# sbc_245.net
KiCad netlist of a schematic drawn in EAGLE
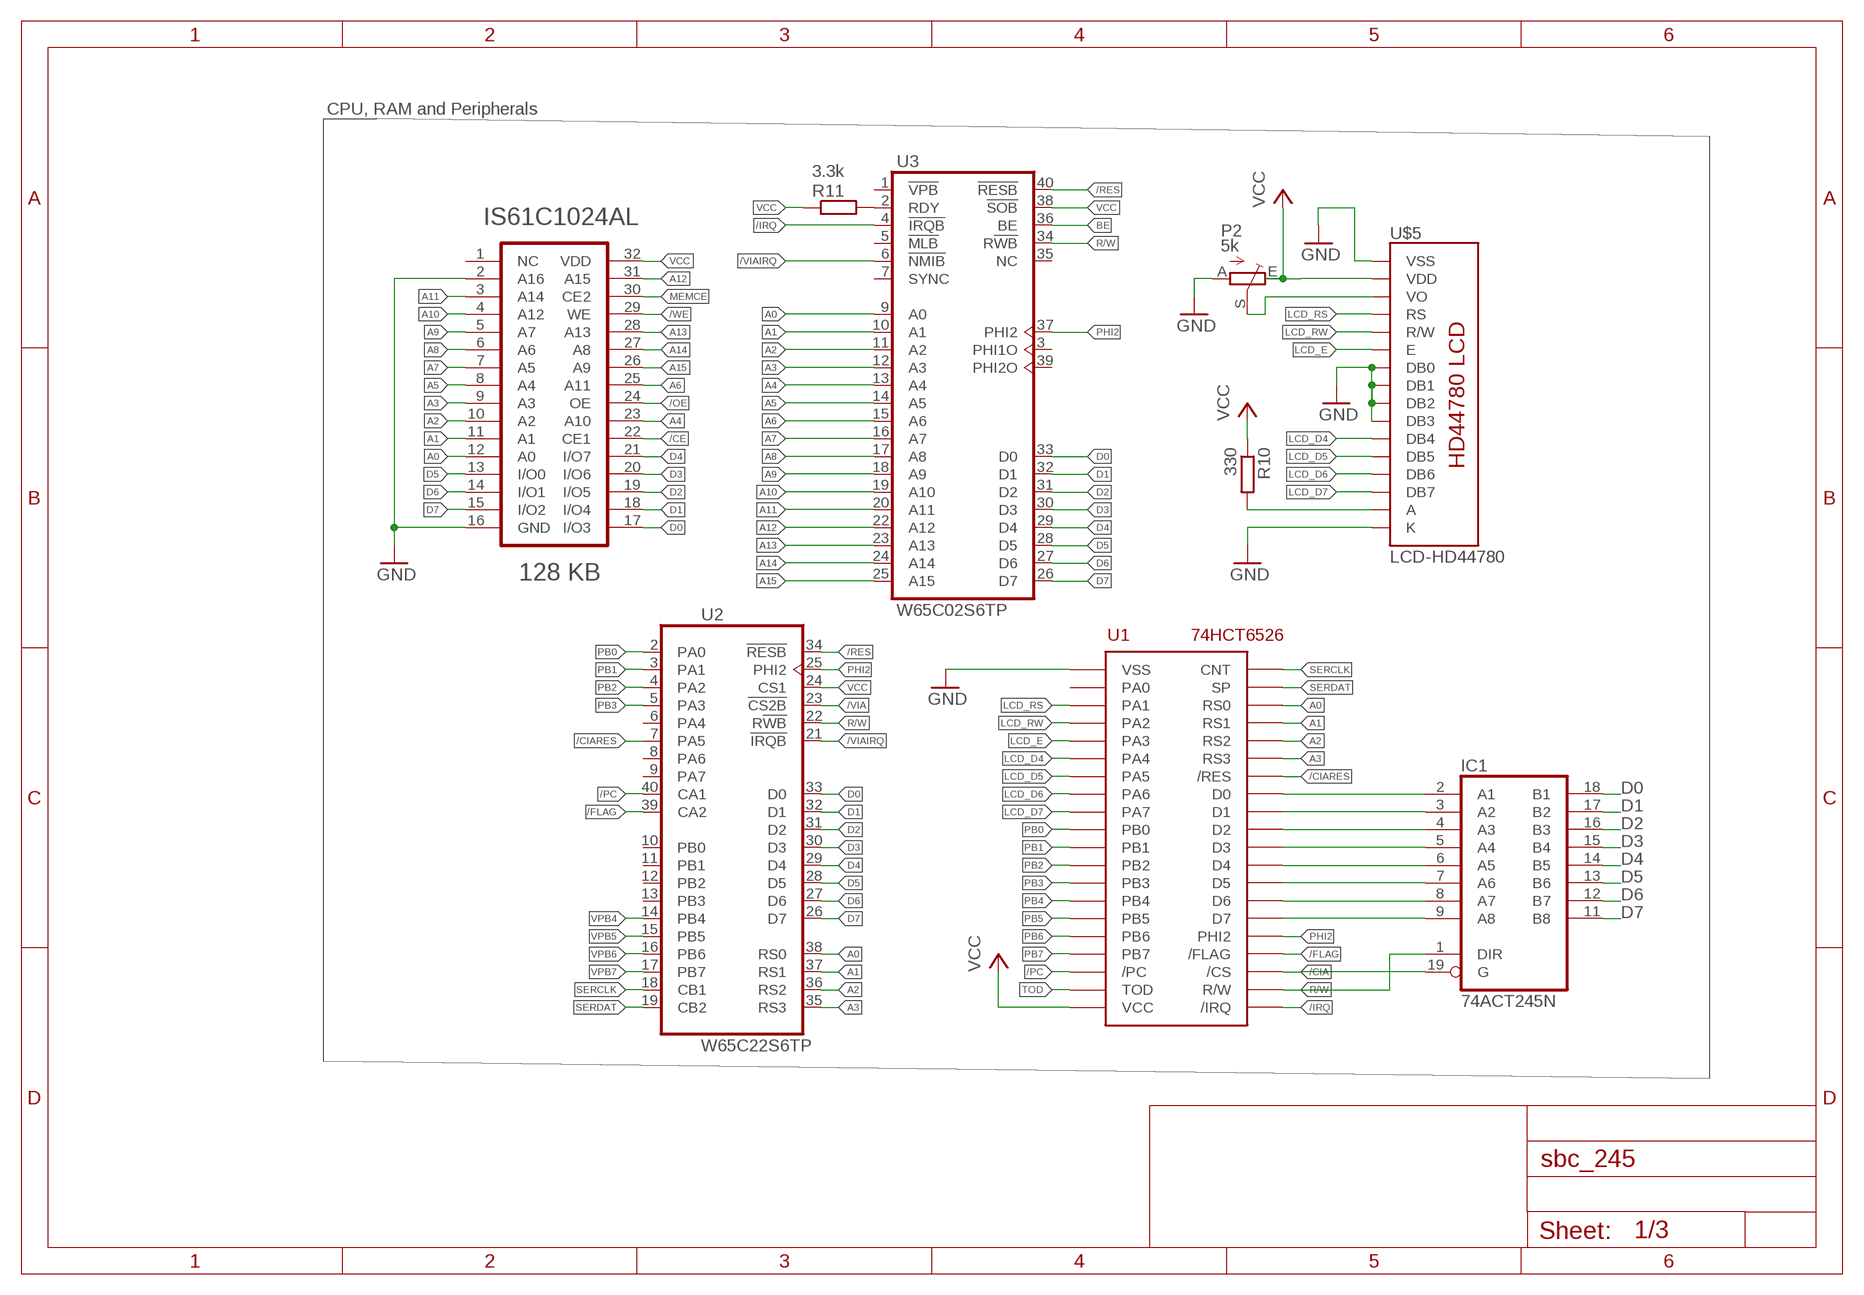
[diagram p0: schematic, sheet 1]
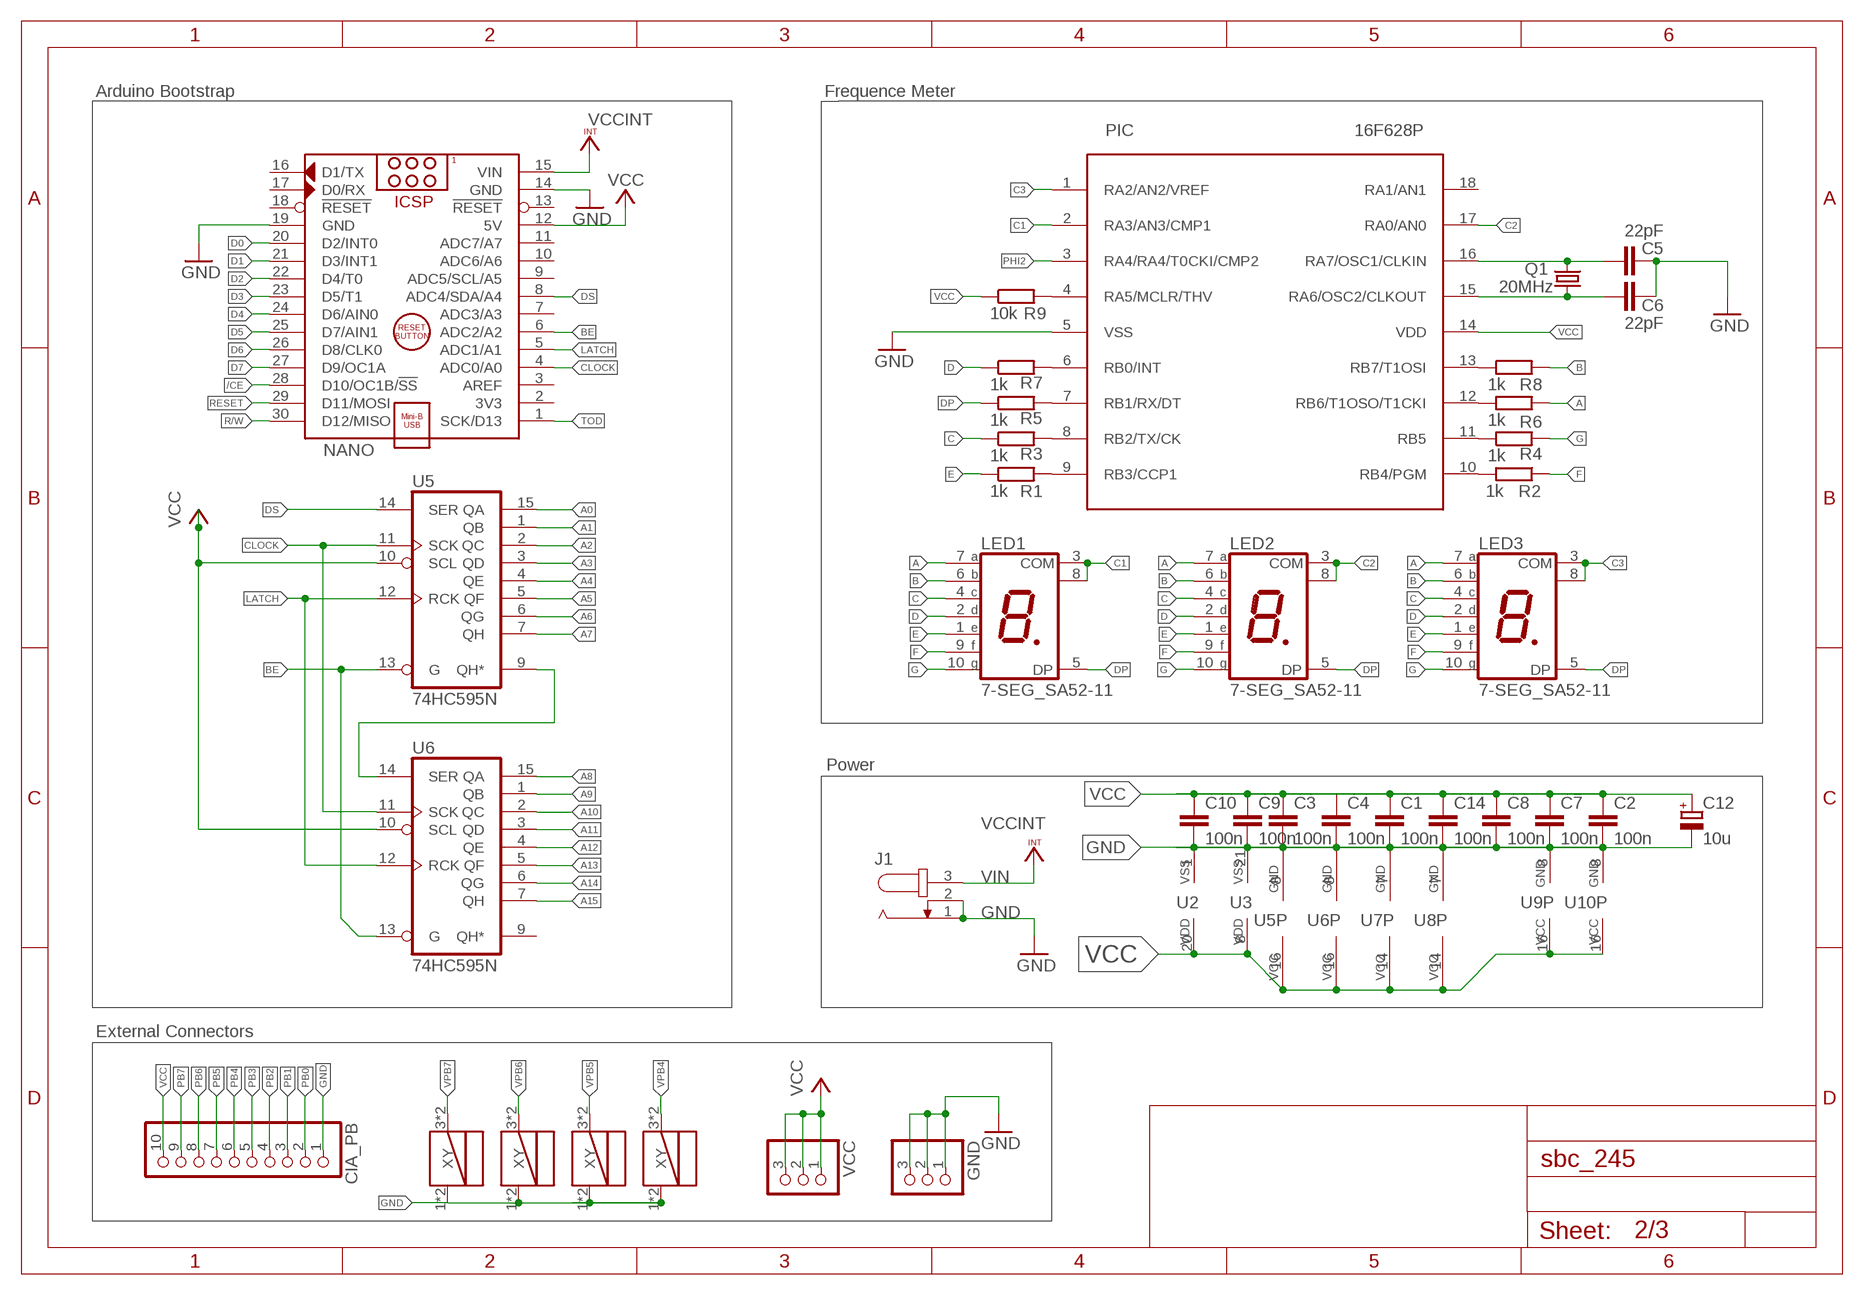
[diagram p1: schematic, sheet 2]
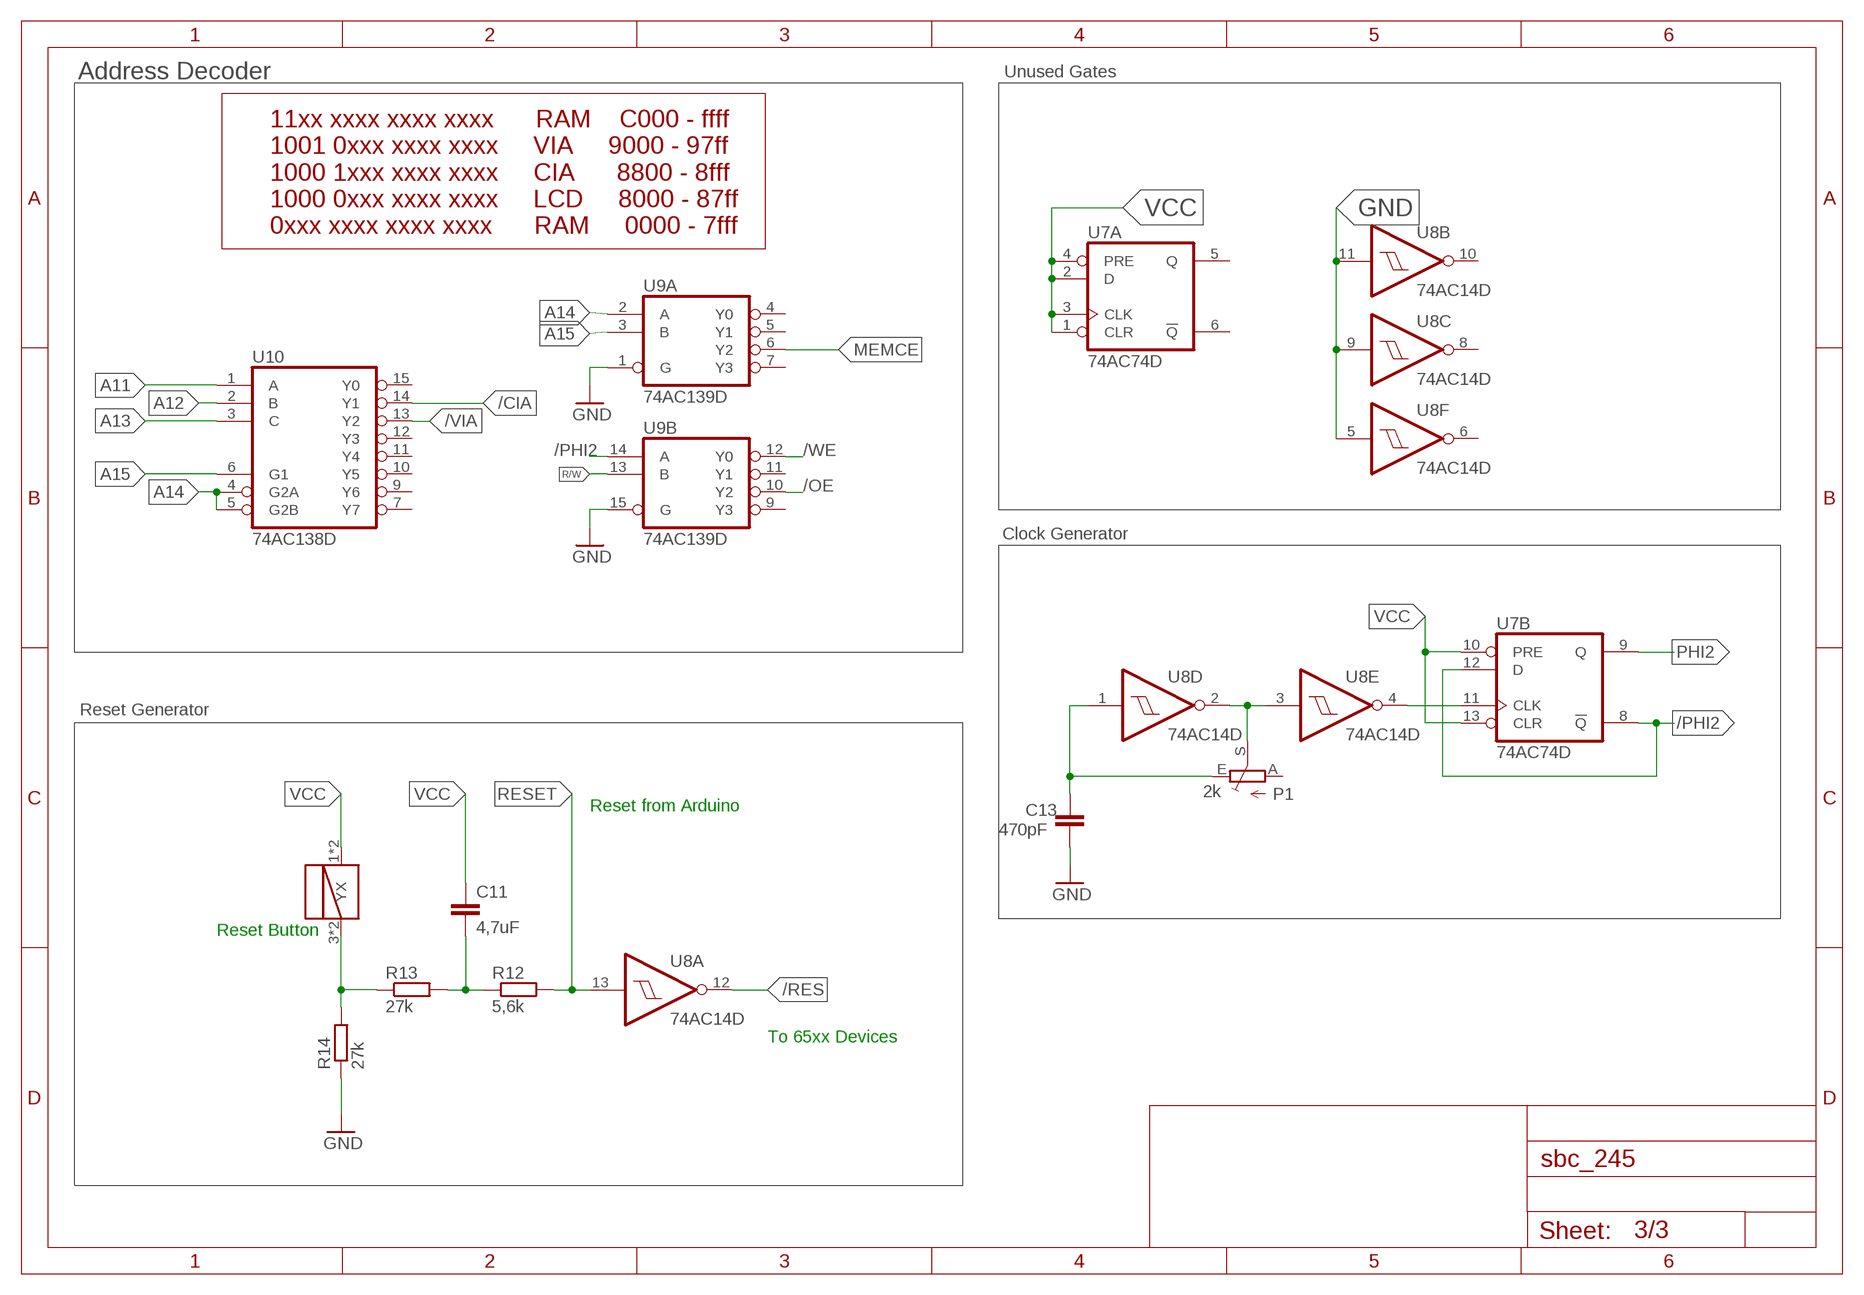
[diagram p2: schematic, sheet 3]

(export (version "E")
  (design (tool "Eeschema 10.0.6"))
  (components
    (comp (ref "C1")
      (value "100n")
      (footprint "eagle-import:C0805")
      (libsource (lib "eagle-import") (part "C-EUC0805"))
    )
    (comp (ref "C2")
      (value "100n")
      (footprint "eagle-import:C0805")
      (libsource (lib "eagle-import") (part "C-EUC0805"))
    )
    (comp (ref "C3")
      (value "100n")
      (footprint "eagle-import:C0805")
      (libsource (lib "eagle-import") (part "C-EUC0805"))
    )
    (comp (ref "C4")
      (value "100n")
      (footprint "eagle-import:C0805")
      (libsource (lib "eagle-import") (part "C-EUC0805"))
    )
    (comp (ref "C5")
      (value "22pF")
      (footprint "eagle-import:C025-025X050")
      (libsource (lib "eagle-import") (part "C-EU025-025X050"))
    )
    (comp (ref "C6")
      (value "22pF")
      (footprint "eagle-import:C025-025X050")
      (libsource (lib "eagle-import") (part "C-EU025-025X050"))
    )
    (comp (ref "C7")
      (value "100n")
      (footprint "eagle-import:C0805")
      (libsource (lib "eagle-import") (part "C-EUC0805"))
    )
    (comp (ref "C8")
      (value "100n")
      (footprint "eagle-import:C0805")
      (libsource (lib "eagle-import") (part "C-EUC0805"))
    )
    (comp (ref "C9")
      (value "100n")
      (footprint "eagle-import:C0805")
      (libsource (lib "eagle-import") (part "C-EUC0805"))
    )
    (comp (ref "C10")
      (value "100n")
      (footprint "eagle-import:C0805")
      (libsource (lib "eagle-import") (part "C-EUC0805"))
    )
    (comp (ref "C12")
      (value "10u")
      (footprint "eagle-import:B45181A")
      (libsource (lib "eagle-import") (part "CPOL-EUB45181A"))
    )
    (comp (ref "C14")
      (value "100n")
      (footprint "eagle-import:C0805")
      (libsource (lib "eagle-import") (part "C-EUC0805"))
    )
    (comp (ref "CIA_PB")
      (value "PINHD-1X10")
      (footprint "eagle-import:1X10")
      (libsource (lib "eagle-import") (part "PINHD-1X10"))
    )
    (comp (ref "GND")
      (value "PINHD-1X3")
      (footprint "eagle-import:1X03")
      (libsource (lib "eagle-import") (part "PINHD-1X3"))
    )
    (comp (ref "J1")
      (value "JACK-PLUG0")
      (footprint "eagle-import:SPC4077")
      (libsource (lib "eagle-import") (part "JACK-PLUG0"))
    )
    (comp (ref "LED1")
      (value "7-SEG_SA52-11")
      (footprint "eagle-import:SA52-11")
      (libsource (lib "eagle-import") (part "7-SEG_SA52-11"))
    )
    (comp (ref "LED2")
      (value "7-SEG_SA52-11")
      (footprint "eagle-import:SA52-11")
      (libsource (lib "eagle-import") (part "7-SEG_SA52-11"))
    )
    (comp (ref "LED3")
      (value "7-SEG_SA52-11")
      (footprint "eagle-import:SA52-11")
      (libsource (lib "eagle-import") (part "7-SEG_SA52-11"))
    )
    (comp (ref "NANO")
      (value "ARDUINO_NANO")
      (footprint "eagle-import:ARDUINO_NANO")
      (libsource (lib "eagle-import") (part "ARDUINO_NANO"))
    )
    (comp (ref "PIC")
      (value "16F628P")
      (footprint "eagle-import:DIL18")
      (libsource (lib "eagle-import") (part "16F62P8"))
    )
    (comp (ref "Q1")
      (value "20MHz")
      (footprint "eagle-import:HC18U-V")
      (libsource (lib "eagle-import") (part "CRYSTALHC18U-V"))
    )
    (comp (ref "R1")
      (value "1k")
      (footprint "eagle-import:0207_7")
      (libsource (lib "eagle-import") (part "R-EU_0207/7"))
    )
    (comp (ref "R2")
      (value "1k")
      (footprint "eagle-import:0207_7")
      (libsource (lib "eagle-import") (part "R-EU_0207/7"))
    )
    (comp (ref "R3")
      (value "1k")
      (footprint "eagle-import:0207_7")
      (libsource (lib "eagle-import") (part "R-EU_0207/7"))
    )
    (comp (ref "R4")
      (value "1k")
      (footprint "eagle-import:0207_7")
      (libsource (lib "eagle-import") (part "R-EU_0207/7"))
    )
    (comp (ref "R5")
      (value "1k")
      (footprint "eagle-import:0207_7")
      (libsource (lib "eagle-import") (part "R-EU_0207/7"))
    )
    (comp (ref "R6")
      (value "1k")
      (footprint "eagle-import:0207_7")
      (libsource (lib "eagle-import") (part "R-EU_0207/7"))
    )
    (comp (ref "R7")
      (value "1k")
      (footprint "eagle-import:0207_7")
      (libsource (lib "eagle-import") (part "R-EU_0207/7"))
    )
    (comp (ref "R8")
      (value "1k")
      (footprint "eagle-import:0207_7")
      (libsource (lib "eagle-import") (part "R-EU_0207/7"))
    )
    (comp (ref "R9")
      (value "10k")
      (footprint "eagle-import:R0805")
      (libsource (lib "eagle-import") (part "R-EU_R0805"))
    )
    (comp (ref "U$1")
      (value "TSA451G90-250")
      (footprint "eagle-import:TSA451G90-250")
      (libsource (lib "eagle-import") (part "TSA451G90-250"))
    )
    (comp (ref "U$2")
      (value "TSA451G90-250")
      (footprint "eagle-import:TSA451G90-250")
      (libsource (lib "eagle-import") (part "TSA451G90-250"))
    )
    (comp (ref "U$3")
      (value "TSA451G90-250")
      (footprint "eagle-import:TSA451G90-250")
      (libsource (lib "eagle-import") (part "TSA451G90-250"))
    )
    (comp (ref "U$4")
      (value "TSA451G90-250")
      (footprint "eagle-import:TSA451G90-250")
      (libsource (lib "eagle-import") (part "TSA451G90-250"))
    )
    (comp (ref "U2")
      (value "W65C22S6TP")
      (footprint "eagle-import:DIL40")
      (libsource (lib "eagle-import") (part "W65C22SP6T"))
    )
    (comp (ref "U3")
      (value "W65C02S6TP")
      (footprint "eagle-import:DIL40")
      (libsource (lib "eagle-import") (part "W65C02SP6T"))
    )
    (comp (ref "U5")
      (value "74HC595N")
      (footprint "eagle-import:SO16")
      (libsource (lib "eagle-import") (part "74595DLS"))
    )
    (comp (ref "U6")
      (value "74HC595N")
      (footprint "eagle-import:SO16")
      (libsource (lib "eagle-import") (part "74595DLS"))
    )
    (comp (ref "U7")
      (value "74AC74D")
      (footprint "eagle-import:SO14")
      (libsource (lib "eagle-import") (part "7474DLS"))
    )
    (comp (ref "U8")
      (value "74AC14D")
      (footprint "eagle-import:SO14")
      (libsource (lib "eagle-import") (part "7414D"))
    )
    (comp (ref "U9")
      (value "74AC139D")
      (footprint "eagle-import:SO16")
      (libsource (lib "eagle-import") (part "74139DAC"))
    )
    (comp (ref "U10")
      (value "74AC138D")
      (footprint "eagle-import:SO16")
      (libsource (lib "eagle-import") (part "74138DAC"))
    )
    (comp (ref "VCC")
      (value "PINHD-1X3")
      (footprint "eagle-import:1X03")
      (libsource (lib "eagle-import") (part "PINHD-1X3"))
    )
    (comp (ref "IC1")
      (value "74ACT245N")
      (footprint "eagle-import:DIL20")
      (libsource (lib "eagle-import") (part "74245NACT"))
    )
    (comp (ref "P2")
      (value "5k")
      (footprint "eagle-import:B64Y")
      (libsource (lib "eagle-import") (part "TRIM_EU-B64Y"))
    )
    (comp (ref "R10")
      (value "330")
      (footprint "eagle-import:R0805")
      (libsource (lib "eagle-import") (part "R-EU_R0805"))
    )
    (comp (ref "R11")
      (value "3.3k")
      (footprint "eagle-import:R0805")
      (libsource (lib "eagle-import") (part "R-EU_R0805"))
    )
    (comp (ref "U$5")
      (value "LCD-HD44780")
      (footprint "eagle-import:LCD-20X4-4HOLES2X8")
      (libsource (lib "eagle-import") (part "LCD-HD44780"))
    )
    (comp (ref "U1")
      (value "74HCT6526")
      (footprint "eagle-import:DIP40")
      (libsource (lib "eagle-import") (part "CIA40CIA_DIP"))
    )
    (comp (ref "U4")
      (value "IS61C1024AL-12JLI-TR")
      (footprint "eagle-import:SOJ32_3")
      (libsource (lib "eagle-import") (part "IS61C1024AL"))
    )
    (comp (ref "C11")
      (value "4,7uF")
      (footprint "eagle-import:C0805")
      (libsource (lib "eagle-import") (part "C-EUC0805"))
    )
    (comp (ref "C13")
      (value "470pF")
      (footprint "eagle-import:C0805")
      (libsource (lib "eagle-import") (part "C-EUC0805"))
    )
    (comp (ref "P1")
      (value "2k")
      (footprint "eagle-import:B64Y")
      (libsource (lib "eagle-import") (part "TRIM_EU-B64Y"))
    )
    (comp (ref "R12")
      (value "5,6k")
      (footprint "eagle-import:R0805")
      (libsource (lib "eagle-import") (part "R-EU_R0805"))
    )
    (comp (ref "R13")
      (value "27k")
      (footprint "eagle-import:R0805")
      (libsource (lib "eagle-import") (part "R-EU_R0805"))
    )
    (comp (ref "R14")
      (value "27k")
      (footprint "eagle-import:R0805")
      (libsource (lib "eagle-import") (part "R-EU_R0805"))
    )
    (comp (ref "SW1")
      (value "TSA451G90-250")
      (footprint "eagle-import:TSA451G90-250")
      (libsource (lib "eagle-import") (part "TSA451G90-250"))
    )
  )
  (nets
    (net (code "1") (name "A") (class "Default")
      (node (ref "LED1") (pin "7") (pinfunction "A_7") (pintype "passive"))
      (node (ref "LED2") (pin "7") (pinfunction "A_7") (pintype "passive"))
      (node (ref "LED3") (pin "7") (pinfunction "A_7") (pintype "passive"))
      (node (ref "R6") (pin "2") (pinfunction "2_2") (pintype "passive"))
    )
    (net (code "2") (name "A0") (class "Default")
      (node (ref "U1") (pin "38") (pinfunction "RS0_38") (pintype "bidirectional"))
      (node (ref "U2") (pin "38") (pinfunction "RS0_38") (pintype "input"))
      (node (ref "U3") (pin "9") (pinfunction "A0_9") (pintype "output"))
      (node (ref "U4") (pin "12") (pinfunction "A0_12") (pintype "bidirectional"))
      (node (ref "U5") (pin "15") (pinfunction "QA_15") (pintype "tri_state"))
    )
    (net (code "3") (name "A1") (class "Default")
      (node (ref "U1") (pin "37") (pinfunction "RS1_37") (pintype "bidirectional"))
      (node (ref "U2") (pin "37") (pinfunction "RS1_37") (pintype "input"))
      (node (ref "U3") (pin "10") (pinfunction "A1_10") (pintype "output"))
      (node (ref "U4") (pin "11") (pinfunction "A1_11") (pintype "bidirectional"))
      (node (ref "U5") (pin "1") (pinfunction "QB_1") (pintype "tri_state"))
    )
    (net (code "4") (name "A2") (class "Default")
      (node (ref "U1") (pin "36") (pinfunction "RS2_36") (pintype "bidirectional"))
      (node (ref "U2") (pin "36") (pinfunction "RS2_36") (pintype "input"))
      (node (ref "U3") (pin "11") (pinfunction "A2_11") (pintype "output"))
      (node (ref "U4") (pin "10") (pinfunction "A2_10") (pintype "bidirectional"))
      (node (ref "U5") (pin "2") (pinfunction "QC_2") (pintype "tri_state"))
    )
    (net (code "5") (name "A3") (class "Default")
      (node (ref "U1") (pin "35") (pinfunction "RS3_35") (pintype "bidirectional"))
      (node (ref "U2") (pin "35") (pinfunction "RS3_35") (pintype "input"))
      (node (ref "U3") (pin "12") (pinfunction "A3_12") (pintype "output"))
      (node (ref "U4") (pin "9") (pinfunction "A3_9") (pintype "bidirectional"))
      (node (ref "U5") (pin "3") (pinfunction "QD_3") (pintype "tri_state"))
    )
    (net (code "6") (name "A4") (class "Default")
      (node (ref "U3") (pin "13") (pinfunction "A4_13") (pintype "output"))
      (node (ref "U4") (pin "23") (pinfunction "A10_23") (pintype "bidirectional"))
      (node (ref "U5") (pin "4") (pinfunction "QE_4") (pintype "tri_state"))
    )
    (net (code "7") (name "A5") (class "Default")
      (node (ref "U3") (pin "14") (pinfunction "A5_14") (pintype "output"))
      (node (ref "U4") (pin "8") (pinfunction "A4_8") (pintype "bidirectional"))
      (node (ref "U5") (pin "5") (pinfunction "QF_5") (pintype "tri_state"))
    )
    (net (code "8") (name "A6") (class "Default")
      (node (ref "U3") (pin "15") (pinfunction "A6_15") (pintype "output"))
      (node (ref "U4") (pin "25") (pinfunction "A11_25") (pintype "bidirectional"))
      (node (ref "U5") (pin "6") (pinfunction "QG_6") (pintype "tri_state"))
    )
    (net (code "9") (name "A7") (class "Default")
      (node (ref "U3") (pin "16") (pinfunction "A7_16") (pintype "output"))
      (node (ref "U4") (pin "7") (pinfunction "A5_7") (pintype "bidirectional"))
      (node (ref "U5") (pin "7") (pinfunction "QH_7") (pintype "tri_state"))
    )
    (net (code "10") (name "A8") (class "Default")
      (node (ref "U3") (pin "17") (pinfunction "A8_17") (pintype "output"))
      (node (ref "U4") (pin "6") (pinfunction "A6_6") (pintype "bidirectional"))
      (node (ref "U6") (pin "15") (pinfunction "QA_15") (pintype "tri_state"))
    )
    (net (code "11") (name "A9") (class "Default")
      (node (ref "U3") (pin "18") (pinfunction "A9_18") (pintype "output"))
      (node (ref "U4") (pin "5") (pinfunction "A7_5") (pintype "bidirectional"))
      (node (ref "U6") (pin "1") (pinfunction "QB_1") (pintype "tri_state"))
    )
    (net (code "12") (name "A10") (class "Default")
      (node (ref "U3") (pin "19") (pinfunction "A10_19") (pintype "output"))
      (node (ref "U4") (pin "4") (pinfunction "A12_4") (pintype "bidirectional"))
      (node (ref "U6") (pin "2") (pinfunction "QC_2") (pintype "tri_state"))
    )
    (net (code "13") (name "A11") (class "Default")
      (node (ref "U10") (pin "1") (pinfunction "A_1") (pintype "input"))
      (node (ref "U3") (pin "20") (pinfunction "A11_20") (pintype "output"))
      (node (ref "U4") (pin "3") (pinfunction "A14_3") (pintype "bidirectional"))
      (node (ref "U6") (pin "3") (pinfunction "QD_3") (pintype "tri_state"))
    )
    (net (code "14") (name "A12") (class "Default")
      (node (ref "U10") (pin "2") (pinfunction "B_2") (pintype "input"))
      (node (ref "U3") (pin "22") (pinfunction "A12_22") (pintype "output"))
      (node (ref "U4") (pin "31") (pinfunction "A15_31") (pintype "bidirectional"))
      (node (ref "U6") (pin "4") (pinfunction "QE_4") (pintype "tri_state"))
    )
    (net (code "15") (name "A13") (class "Default")
      (node (ref "U10") (pin "3") (pinfunction "C_3") (pintype "input"))
      (node (ref "U3") (pin "23") (pinfunction "A13_23") (pintype "output"))
      (node (ref "U4") (pin "28") (pinfunction "A13_28") (pintype "bidirectional"))
      (node (ref "U6") (pin "5") (pinfunction "QF_5") (pintype "tri_state"))
    )
    (net (code "16") (name "A14") (class "Default")
      (node (ref "U10") (pin "4") (pinfunction "G2A_4") (pintype "input"))
      (node (ref "U10") (pin "5") (pinfunction "G2B_5") (pintype "input"))
      (node (ref "U3") (pin "24") (pinfunction "A14_24") (pintype "output"))
      (node (ref "U4") (pin "27") (pinfunction "A8_27") (pintype "bidirectional"))
      (node (ref "U6") (pin "6") (pinfunction "QG_6") (pintype "tri_state"))
      (node (ref "U9") (pin "2") (pinfunction "A_2") (pintype "input"))
    )
    (net (code "17") (name "A15") (class "Default")
      (node (ref "U10") (pin "6") (pinfunction "G1_6") (pintype "input"))
      (node (ref "U3") (pin "25") (pinfunction "A15_25") (pintype "output"))
      (node (ref "U4") (pin "26") (pinfunction "A9_26") (pintype "bidirectional"))
      (node (ref "U6") (pin "7") (pinfunction "QH_7") (pintype "tri_state"))
      (node (ref "U9") (pin "3") (pinfunction "B_3") (pintype "input"))
    )
    (net (code "18") (name "B") (class "Default")
      (node (ref "LED1") (pin "6") (pinfunction "B_6") (pintype "passive"))
      (node (ref "LED2") (pin "6") (pinfunction "B_6") (pintype "passive"))
      (node (ref "LED3") (pin "6") (pinfunction "B_6") (pintype "passive"))
      (node (ref "R8") (pin "2") (pinfunction "2_2") (pintype "passive"))
    )
    (net (code "19") (name "BE") (class "Default")
      (node (ref "NANO") (pin "6") (pinfunction "ADC2/A2_6") (pintype "bidirectional"))
      (node (ref "U3") (pin "36") (pinfunction "BE_36") (pintype "input"))
      (node (ref "U5") (pin "13") (pinfunction "G_13") (pintype "input"))
      (node (ref "U6") (pin "13") (pinfunction "G_13") (pintype "input"))
    )
    (net (code "20") (name "C") (class "Default")
      (node (ref "LED1") (pin "4") (pinfunction "C_4") (pintype "passive"))
      (node (ref "LED2") (pin "4") (pinfunction "C_4") (pintype "passive"))
      (node (ref "LED3") (pin "4") (pinfunction "C_4") (pintype "passive"))
      (node (ref "R3") (pin "1") (pinfunction "1_1") (pintype "passive"))
    )
    (net (code "21") (name "C1") (class "Default")
      (node (ref "LED1") (pin "3") (pinfunction "COM_3") (pintype "passive"))
      (node (ref "LED1") (pin "8") (pinfunction "COM_8") (pintype "passive"))
      (node (ref "PIC") (pin "2") (pinfunction "RA3/AN3/CMP1_2") (pintype "bidirectional"))
    )
    (net (code "22") (name "C2") (class "Default")
      (node (ref "LED2") (pin "3") (pinfunction "COM_3") (pintype "passive"))
      (node (ref "LED2") (pin "8") (pinfunction "COM_8") (pintype "passive"))
      (node (ref "PIC") (pin "17") (pinfunction "RA0/AN0_17") (pintype "bidirectional"))
    )
    (net (code "23") (name "C3") (class "Default")
      (node (ref "LED3") (pin "3") (pinfunction "COM_3") (pintype "passive"))
      (node (ref "LED3") (pin "8") (pinfunction "COM_8") (pintype "passive"))
      (node (ref "PIC") (pin "1") (pinfunction "RA2/AN2/VREF_1") (pintype "bidirectional"))
    )
    (net (code "24") (name "CLOCK") (class "Default")
      (node (ref "NANO") (pin "4") (pinfunction "ADC0/A0_4") (pintype "bidirectional"))
      (node (ref "U5") (pin "11") (pinfunction "SCK_11") (pintype "input"))
      (node (ref "U6") (pin "11") (pinfunction "SCK_11") (pintype "input"))
    )
    (net (code "25") (name "D") (class "Default")
      (node (ref "LED1") (pin "2") (pinfunction "D_2") (pintype "passive"))
      (node (ref "LED2") (pin "2") (pinfunction "D_2") (pintype "passive"))
      (node (ref "LED3") (pin "2") (pinfunction "D_2") (pintype "passive"))
      (node (ref "R7") (pin "1") (pinfunction "1_1") (pintype "passive"))
    )
    (net (code "26") (name "D0") (class "Default")
      (node (ref "IC1") (pin "18") (pinfunction "B1_18") (pintype "bidirectional"))
      (node (ref "NANO") (pin "20") (pinfunction "D2/INT0_20") (pintype "bidirectional"))
      (node (ref "U2") (pin "33") (pinfunction "D0_33") (pintype "bidirectional"))
      (node (ref "U3") (pin "33") (pinfunction "D0_33") (pintype "bidirectional"))
      (node (ref "U4") (pin "17") (pinfunction "I/O3_17") (pintype "bidirectional"))
    )
    (net (code "27") (name "D1") (class "Default")
      (node (ref "IC1") (pin "17") (pinfunction "B2_17") (pintype "bidirectional"))
      (node (ref "NANO") (pin "21") (pinfunction "D3/INT1_21") (pintype "bidirectional"))
      (node (ref "U2") (pin "32") (pinfunction "D1_32") (pintype "bidirectional"))
      (node (ref "U3") (pin "32") (pinfunction "D1_32") (pintype "bidirectional"))
      (node (ref "U4") (pin "18") (pinfunction "I/O4_18") (pintype "bidirectional"))
    )
    (net (code "28") (name "D2") (class "Default")
      (node (ref "IC1") (pin "16") (pinfunction "B3_16") (pintype "bidirectional"))
      (node (ref "NANO") (pin "22") (pinfunction "D4/T0_22") (pintype "bidirectional"))
      (node (ref "U2") (pin "31") (pinfunction "D2_31") (pintype "bidirectional"))
      (node (ref "U3") (pin "31") (pinfunction "D2_31") (pintype "bidirectional"))
      (node (ref "U4") (pin "19") (pinfunction "I/O5_19") (pintype "bidirectional"))
    )
    (net (code "29") (name "D3") (class "Default")
      (node (ref "IC1") (pin "15") (pinfunction "B4_15") (pintype "bidirectional"))
      (node (ref "NANO") (pin "23") (pinfunction "D5/T1_23") (pintype "bidirectional"))
      (node (ref "U2") (pin "30") (pinfunction "D3_30") (pintype "bidirectional"))
      (node (ref "U3") (pin "30") (pinfunction "D3_30") (pintype "bidirectional"))
      (node (ref "U4") (pin "20") (pinfunction "I/O6_20") (pintype "bidirectional"))
    )
    (net (code "30") (name "D4") (class "Default")
      (node (ref "IC1") (pin "14") (pinfunction "B5_14") (pintype "bidirectional"))
      (node (ref "NANO") (pin "24") (pinfunction "D6/AIN0_24") (pintype "bidirectional"))
      (node (ref "U2") (pin "29") (pinfunction "D4_29") (pintype "bidirectional"))
      (node (ref "U3") (pin "29") (pinfunction "D4_29") (pintype "bidirectional"))
      (node (ref "U4") (pin "21") (pinfunction "I/O7_21") (pintype "bidirectional"))
    )
    (net (code "31") (name "D5") (class "Default")
      (node (ref "IC1") (pin "13") (pinfunction "B6_13") (pintype "bidirectional"))
      (node (ref "NANO") (pin "25") (pinfunction "D7/AIN1_25") (pintype "bidirectional"))
      (node (ref "U2") (pin "28") (pinfunction "D5_28") (pintype "bidirectional"))
      (node (ref "U3") (pin "28") (pinfunction "D5_28") (pintype "bidirectional"))
      (node (ref "U4") (pin "13") (pinfunction "I/O0_13") (pintype "bidirectional"))
    )
    (net (code "32") (name "D6") (class "Default")
      (node (ref "IC1") (pin "12") (pinfunction "B7_12") (pintype "bidirectional"))
      (node (ref "NANO") (pin "26") (pinfunction "D8/CLK0_26") (pintype "bidirectional"))
      (node (ref "U2") (pin "27") (pinfunction "D6_27") (pintype "bidirectional"))
      (node (ref "U3") (pin "27") (pinfunction "D6_27") (pintype "bidirectional"))
      (node (ref "U4") (pin "14") (pinfunction "I/O1_14") (pintype "bidirectional"))
    )
    (net (code "33") (name "D7") (class "Default")
      (node (ref "IC1") (pin "11") (pinfunction "B8_11") (pintype "bidirectional"))
      (node (ref "NANO") (pin "27") (pinfunction "D9/OC1A_27") (pintype "bidirectional"))
      (node (ref "U2") (pin "26") (pinfunction "D7_26") (pintype "bidirectional"))
      (node (ref "U3") (pin "26") (pinfunction "D7_26") (pintype "bidirectional"))
      (node (ref "U4") (pin "15") (pinfunction "I/O2_15") (pintype "bidirectional"))
    )
    (net (code "34") (name "DP") (class "Default")
      (node (ref "LED1") (pin "5") (pinfunction "DP_5") (pintype "passive"))
      (node (ref "LED2") (pin "5") (pinfunction "DP_5") (pintype "passive"))
      (node (ref "LED3") (pin "5") (pinfunction "DP_5") (pintype "passive"))
      (node (ref "R5") (pin "1") (pinfunction "1_1") (pintype "passive"))
    )
    (net (code "35") (name "DS") (class "Default")
      (node (ref "NANO") (pin "8") (pinfunction "ADC4/SDA/A4_8") (pintype "bidirectional"))
      (node (ref "U5") (pin "14") (pinfunction "SER_14") (pintype "input"))
    )
    (net (code "36") (name "E") (class "Default")
      (node (ref "LED1") (pin "1") (pinfunction "E_1") (pintype "passive"))
      (node (ref "LED2") (pin "1") (pinfunction "E_1") (pintype "passive"))
      (node (ref "LED3") (pin "1") (pinfunction "E_1") (pintype "passive"))
      (node (ref "R1") (pin "1") (pinfunction "1_1") (pintype "passive"))
    )
    (net (code "37") (name "F") (class "Default")
      (node (ref "LED1") (pin "9") (pinfunction "F_9") (pintype "passive"))
      (node (ref "LED2") (pin "9") (pinfunction "F_9") (pintype "passive"))
      (node (ref "LED3") (pin "9") (pinfunction "F_9") (pintype "passive"))
      (node (ref "R2") (pin "1") (pinfunction "1_1") (pintype "passive"))
    )
    (net (code "38") (name "G") (class "Default")
      (node (ref "LED1") (pin "10") (pinfunction "G_10") (pintype "passive"))
      (node (ref "LED2") (pin "10") (pinfunction "G_10") (pintype "passive"))
      (node (ref "LED3") (pin "10") (pinfunction "G_10") (pintype "passive"))
      (node (ref "R4") (pin "2") (pinfunction "2_2") (pintype "passive"))
    )
    (net (code "39") (name "GND") (class "Default")
      (node (ref "C1") (pin "2") (pinfunction "2_2") (pintype "passive"))
      (node (ref "C10") (pin "2") (pinfunction "2_2") (pintype "passive"))
      (node (ref "C12") (pin "-") (pinfunction "-_-") (pintype "passive"))
      (node (ref "C13") (pin "2") (pinfunction "2_2") (pintype "passive"))
      (node (ref "C14") (pin "2") (pinfunction "2_2") (pintype "passive"))
      (node (ref "C2") (pin "2") (pinfunction "2_2") (pintype "passive"))
      (node (ref "C3") (pin "2") (pinfunction "2_2") (pintype "passive"))
      (node (ref "C4") (pin "2") (pinfunction "2_2") (pintype "passive"))
      (node (ref "C5") (pin "2") (pinfunction "2_2") (pintype "passive"))
      (node (ref "C6") (pin "2") (pinfunction "2_2") (pintype "passive"))
      (node (ref "C7") (pin "2") (pinfunction "2_2") (pintype "passive"))
      (node (ref "C8") (pin "2") (pinfunction "2_2") (pintype "passive"))
      (node (ref "C9") (pin "2") (pinfunction "2_2") (pintype "passive"))
      (node (ref "CIA_PB") (pin "1") (pinfunction "1_1") (pintype "passive"))
      (node (ref "GND") (pin "1") (pinfunction "1_1") (pintype "passive"))
      (node (ref "GND") (pin "2") (pinfunction "2_2") (pintype "passive"))
      (node (ref "GND") (pin "3") (pinfunction "3_3") (pintype "passive"))
      (node (ref "J1") (pin "1") (pinfunction "1_1") (pintype "passive"))
      (node (ref "J1") (pin "2") (pinfunction "2_2") (pintype "passive"))
      (node (ref "NANO") (pin "14") (pinfunction "GND_14") (pintype "power_in"))
      (node (ref "NANO") (pin "19") (pinfunction "GND_19") (pintype "power_in"))
      (node (ref "P2") (pin "A") (pinfunction "A_A") (pintype "passive"))
      (node (ref "PIC") (pin "5") (pinfunction "VSS_5") (pintype "power_in"))
      (node (ref "R14") (pin "1") (pinfunction "1_1") (pintype "passive"))
      (node (ref "U$1") (pin "1") (pinfunction "X_1") (pintype "bidirectional"))
      (node (ref "U$1") (pin "2") (pinfunction "X_2") (pintype "bidirectional"))
      (node (ref "U$2") (pin "1") (pinfunction "X_1") (pintype "bidirectional"))
      (node (ref "U$2") (pin "2") (pinfunction "X_2") (pintype "bidirectional"))
      (node (ref "U$3") (pin "1") (pinfunction "X_1") (pintype "bidirectional"))
      (node (ref "U$3") (pin "2") (pinfunction "X_2") (pintype "bidirectional"))
      (node (ref "U$4") (pin "1") (pinfunction "X_1") (pintype "bidirectional"))
      (node (ref "U$4") (pin "2") (pinfunction "X_2") (pintype "bidirectional"))
      (node (ref "U$5") (pin "P$1") (pinfunction "VSS_P$1") (pintype "power_in"))
      (node (ref "U$5") (pin "P$10") (pinfunction "DB3_P$10") (pintype "bidirectional"))
      (node (ref "U$5") (pin "P$16") (pinfunction "K_P$16") (pintype "power_in"))
      (node (ref "U$5") (pin "P$7") (pinfunction "DB0_P$7") (pintype "bidirectional"))
      (node (ref "U$5") (pin "P$8") (pinfunction "DB1_P$8") (pintype "bidirectional"))
      (node (ref "U$5") (pin "P$9") (pinfunction "DB2_P$9") (pintype "bidirectional"))
      (node (ref "U1") (pin "1") (pinfunction "VSS_1") (pintype "bidirectional"))
      (node (ref "U10") (pin "8") (pinfunction "GND_8") (pintype "power_in"))
      (node (ref "U2") (pin "1") (pinfunction "VSS_1") (pintype "power_in"))
      (node (ref "U3") (pin "21") (pinfunction "VSS_21") (pintype "power_in"))
      (node (ref "U4") (pin "16") (pinfunction "GND_16") (pintype "bidirectional"))
      (node (ref "U4") (pin "2") (pinfunction "A16_2") (pintype "bidirectional"))
      (node (ref "U5") (pin "8") (pinfunction "GND_8") (pintype "power_in"))
      (node (ref "U6") (pin "8") (pinfunction "GND_8") (pintype "power_in"))
      (node (ref "U7") (pin "7") (pinfunction "GND_7") (pintype "power_in"))
      (node (ref "U8") (pin "11") (pinfunction "I_11") (pintype "input"))
      (node (ref "U8") (pin "5") (pinfunction "I_5") (pintype "input"))
      (node (ref "U8") (pin "7") (pinfunction "GND_7") (pintype "power_in"))
      (node (ref "U8") (pin "9") (pinfunction "I_9") (pintype "input"))
      (node (ref "U9") (pin "1") (pinfunction "G_1") (pintype "input"))
      (node (ref "U9") (pin "15") (pinfunction "G_15") (pintype "input"))
      (node (ref "U9") (pin "8") (pinfunction "GND_8") (pintype "power_in"))
    )
    (net (code "40") (name "LATCH") (class "Default")
      (node (ref "NANO") (pin "5") (pinfunction "ADC1/A1_5") (pintype "bidirectional"))
      (node (ref "U5") (pin "12") (pinfunction "RCK_12") (pintype "input"))
      (node (ref "U6") (pin "12") (pinfunction "RCK_12") (pintype "input"))
    )
    (net (code "41") (name "LCD_D4") (class "Default")
      (node (ref "U$5") (pin "P$11") (pinfunction "DB4_P$11") (pintype "bidirectional"))
      (node (ref "U1") (pin "6") (pinfunction "PA4_6") (pintype "bidirectional"))
    )
    (net (code "42") (name "LCD_D5") (class "Default")
      (node (ref "U$5") (pin "P$12") (pinfunction "DB5_P$12") (pintype "bidirectional"))
      (node (ref "U1") (pin "7") (pinfunction "PA5_7") (pintype "bidirectional"))
    )
    (net (code "43") (name "LCD_D6") (class "Default")
      (node (ref "U$5") (pin "P$13") (pinfunction "DB6_P$13") (pintype "bidirectional"))
      (node (ref "U1") (pin "8") (pinfunction "PA6_8") (pintype "bidirectional"))
    )
    (net (code "44") (name "LCD_D7") (class "Default")
      (node (ref "U$5") (pin "P$14") (pinfunction "DB7_P$14") (pintype "bidirectional"))
      (node (ref "U1") (pin "9") (pinfunction "PA7_9") (pintype "bidirectional"))
    )
    (net (code "45") (name "LCD_E") (class "Default")
      (node (ref "U$5") (pin "P$6") (pinfunction "E_P$6") (pintype "input"))
      (node (ref "U1") (pin "5") (pinfunction "PA3_5") (pintype "bidirectional"))
    )
    (net (code "46") (name "LCD_RS") (class "Default")
      (node (ref "U$5") (pin "P$4") (pinfunction "RS_P$4") (pintype "input"))
      (node (ref "U1") (pin "3") (pinfunction "PA1_3") (pintype "bidirectional"))
    )
    (net (code "47") (name "LCD_RW") (class "Default")
      (node (ref "U$5") (pin "P$5") (pinfunction "R/W_P$5") (pintype "input"))
      (node (ref "U1") (pin "4") (pinfunction "PA2_4") (pintype "bidirectional"))
    )
    (net (code "48") (name "MEMCE") (class "Default")
      (node (ref "U4") (pin "30") (pinfunction "CE2_30") (pintype "bidirectional"))
      (node (ref "U9") (pin "6") (pinfunction "Y2_6") (pintype "output"))
    )
    (net (code "49") (name "Net-(C11-Pad2)") (class "Default")
      (node (ref "C11") (pin "2") (pinfunction "2_2") (pintype "passive"))
      (node (ref "R12") (pin "1") (pinfunction "1_1") (pintype "passive"))
      (node (ref "R13") (pin "2") (pinfunction "2_2") (pintype "passive"))
    )
    (net (code "50") (name "Net-(IC1A-A1)") (class "Default")
      (node (ref "IC1") (pin "2") (pinfunction "A1_2") (pintype "bidirectional"))
      (node (ref "U1") (pin "33") (pinfunction "D0_33") (pintype "bidirectional"))
    )
    (net (code "51") (name "Net-(IC1A-A2)") (class "Default")
      (node (ref "IC1") (pin "3") (pinfunction "A2_3") (pintype "bidirectional"))
      (node (ref "U1") (pin "32") (pinfunction "D1_32") (pintype "bidirectional"))
    )
    (net (code "52") (name "Net-(IC1A-A3)") (class "Default")
      (node (ref "IC1") (pin "4") (pinfunction "A3_4") (pintype "bidirectional"))
      (node (ref "U1") (pin "31") (pinfunction "D2_31") (pintype "bidirectional"))
    )
    (net (code "53") (name "Net-(IC1A-A4)") (class "Default")
      (node (ref "IC1") (pin "5") (pinfunction "A4_5") (pintype "bidirectional"))
      (node (ref "U1") (pin "30") (pinfunction "D3_30") (pintype "bidirectional"))
    )
    (net (code "54") (name "Net-(IC1A-A5)") (class "Default")
      (node (ref "IC1") (pin "6") (pinfunction "A5_6") (pintype "bidirectional"))
      (node (ref "U1") (pin "29") (pinfunction "D4_29") (pintype "bidirectional"))
    )
    (net (code "55") (name "Net-(IC1A-A6)") (class "Default")
      (node (ref "IC1") (pin "7") (pinfunction "A6_7") (pintype "bidirectional"))
      (node (ref "U1") (pin "28") (pinfunction "D5_28") (pintype "bidirectional"))
    )
    (net (code "56") (name "Net-(IC1A-A7)") (class "Default")
      (node (ref "IC1") (pin "8") (pinfunction "A7_8") (pintype "bidirectional"))
      (node (ref "U1") (pin "27") (pinfunction "D6_27") (pintype "bidirectional"))
    )
    (net (code "57") (name "Net-(IC1A-A8)") (class "Default")
      (node (ref "IC1") (pin "9") (pinfunction "A8_9") (pintype "bidirectional"))
      (node (ref "U1") (pin "26") (pinfunction "D7_26") (pintype "bidirectional"))
    )
    (net (code "58") (name "Net-(PIC-RA5{slash}MCLR{slash}THV)") (class "Default")
      (node (ref "PIC") (pin "4") (pinfunction "RA5/MCLR/THV_4") (pintype "input"))
      (node (ref "R9") (pin "2") (pinfunction "2_2") (pintype "passive"))
    )
    (net (code "59") (name "Net-(PIC-RA6{slash}OSC2{slash}CLKOUT)") (class "Default")
      (node (ref "C6") (pin "1") (pinfunction "1_1") (pintype "passive"))
      (node (ref "PIC") (pin "15") (pinfunction "RA6/OSC2/CLKOUT_15") (pintype "bidirectional"))
      (node (ref "Q1") (pin "1") (pinfunction "1_1") (pintype "passive"))
    )
    (net (code "60") (name "Net-(PIC-RA7{slash}OSC1{slash}CLKIN)") (class "Default")
      (node (ref "C5") (pin "1") (pinfunction "1_1") (pintype "passive"))
      (node (ref "PIC") (pin "16") (pinfunction "RA7/OSC1/CLKIN_16") (pintype "bidirectional"))
      (node (ref "Q1") (pin "2") (pinfunction "2_2") (pintype "passive"))
    )
    (net (code "61") (name "Net-(PIC-RB0{slash}INT)") (class "Default")
      (node (ref "PIC") (pin "6") (pinfunction "RB0/INT_6") (pintype "bidirectional"))
      (node (ref "R7") (pin "2") (pinfunction "2_2") (pintype "passive"))
    )
    (net (code "62") (name "Net-(PIC-RB1{slash}RX{slash}DT)") (class "Default")
      (node (ref "PIC") (pin "7") (pinfunction "RB1/RX/DT_7") (pintype "bidirectional"))
      (node (ref "R5") (pin "2") (pinfunction "2_2") (pintype "passive"))
    )
    (net (code "63") (name "Net-(PIC-RB2{slash}TX{slash}CK)") (class "Default")
      (node (ref "PIC") (pin "8") (pinfunction "RB2/TX/CK_8") (pintype "bidirectional"))
      (node (ref "R3") (pin "2") (pinfunction "2_2") (pintype "passive"))
    )
    (net (code "64") (name "Net-(PIC-RB3{slash}CCP1)") (class "Default")
      (node (ref "PIC") (pin "9") (pinfunction "RB3/CCP1_9") (pintype "bidirectional"))
      (node (ref "R1") (pin "2") (pinfunction "2_2") (pintype "passive"))
    )
    (net (code "65") (name "Net-(PIC-RB4{slash}PGM)") (class "Default")
      (node (ref "PIC") (pin "10") (pinfunction "RB4/PGM_10") (pintype "bidirectional"))
      (node (ref "R2") (pin "2") (pinfunction "2_2") (pintype "passive"))
    )
    (net (code "66") (name "Net-(PIC-RB5)") (class "Default")
      (node (ref "PIC") (pin "11") (pinfunction "RB5_11") (pintype "bidirectional"))
      (node (ref "R4") (pin "1") (pinfunction "1_1") (pintype "passive"))
    )
    (net (code "67") (name "Net-(PIC-RB6{slash}T1OSO{slash}T1CKI)") (class "Default")
      (node (ref "PIC") (pin "12") (pinfunction "RB6/T1OSO/T1CKI_12") (pintype "bidirectional"))
      (node (ref "R6") (pin "1") (pinfunction "1_1") (pintype "passive"))
    )
    (net (code "68") (name "Net-(PIC-RB7{slash}T1OSI)") (class "Default")
      (node (ref "PIC") (pin "13") (pinfunction "RB7/T1OSI_13") (pintype "bidirectional"))
      (node (ref "R8") (pin "1") (pinfunction "1_1") (pintype "passive"))
    )
    (net (code "69") (name "Net-(R13-Pad1)") (class "Default")
      (node (ref "R13") (pin "1") (pinfunction "1_1") (pintype "passive"))
      (node (ref "R14") (pin "2") (pinfunction "2_2") (pintype "passive"))
      (node (ref "SW1") (pin "3") (pinfunction "Y_3") (pintype "bidirectional"))
      (node (ref "SW1") (pin "4") (pinfunction "Y_4") (pintype "bidirectional"))
    )
    (net (code "70") (name "Net-(U$5-A)") (class "Default")
      (node (ref "R10") (pin "2") (pinfunction "2_2") (pintype "passive"))
      (node (ref "U$5") (pin "P$15") (pinfunction "A_P$15") (pintype "power_in"))
    )
    (net (code "71") (name "Net-(U$5-VO)") (class "Default")
      (node (ref "P2") (pin "S") (pinfunction "S_S") (pintype "passive"))
      (node (ref "U$5") (pin "P$3") (pinfunction "VO_P$3") (pintype "bidirectional"))
    )
    (net (code "72") (name "Net-(U3A-RDY)") (class "Default")
      (node (ref "R11") (pin "2") (pinfunction "2_2") (pintype "passive"))
      (node (ref "U3") (pin "2") (pinfunction "RDY_2") (pintype "input"))
    )
    (net (code "73") (name "Net-(U5A-QH*)") (class "Default")
      (node (ref "U5") (pin "9") (pinfunction "QH*_9") (pintype "tri_state"))
      (node (ref "U6") (pin "14") (pinfunction "SER_14") (pintype "input"))
    )
    (net (code "74") (name "Net-(U7B-CLK)") (class "Default")
      (node (ref "U7") (pin "11") (pinfunction "CLK_11") (pintype "input"))
      (node (ref "U8") (pin "4") (pinfunction "O_4") (pintype "output"))
    )
    (net (code "75") (name "Net-(U8D-I)") (class "Default")
      (node (ref "C13") (pin "1") (pinfunction "1_1") (pintype "passive"))
      (node (ref "P1") (pin "E") (pinfunction "E_E") (pintype "passive"))
      (node (ref "U8") (pin "1") (pinfunction "I_1") (pintype "input"))
    )
    (net (code "76") (name "Net-(U8D-O)") (class "Default")
      (node (ref "P1") (pin "S") (pinfunction "S_S") (pintype "passive"))
      (node (ref "U8") (pin "2") (pinfunction "O_2") (pintype "output"))
      (node (ref "U8") (pin "3") (pinfunction "I_3") (pintype "input"))
    )
    (net (code "77") (name "PB0") (class "Default")
      (node (ref "CIA_PB") (pin "2") (pinfunction "2_2") (pintype "passive"))
      (node (ref "U1") (pin "10") (pinfunction "PB0_10") (pintype "bidirectional"))
      (node (ref "U2") (pin "2") (pinfunction "PA0_2") (pintype "bidirectional"))
    )
    (net (code "78") (name "PB1") (class "Default")
      (node (ref "CIA_PB") (pin "3") (pinfunction "3_3") (pintype "passive"))
      (node (ref "U1") (pin "11") (pinfunction "PB1_11") (pintype "bidirectional"))
      (node (ref "U2") (pin "3") (pinfunction "PA1_3") (pintype "bidirectional"))
    )
    (net (code "79") (name "PB2") (class "Default")
      (node (ref "CIA_PB") (pin "4") (pinfunction "4_4") (pintype "passive"))
      (node (ref "U1") (pin "12") (pinfunction "PB2_12") (pintype "bidirectional"))
      (node (ref "U2") (pin "4") (pinfunction "PA2_4") (pintype "bidirectional"))
    )
    (net (code "80") (name "PB3") (class "Default")
      (node (ref "CIA_PB") (pin "5") (pinfunction "5_5") (pintype "passive"))
      (node (ref "U1") (pin "13") (pinfunction "PB3_13") (pintype "bidirectional"))
      (node (ref "U2") (pin "5") (pinfunction "PA3_5") (pintype "bidirectional"))
    )
    (net (code "81") (name "PB4") (class "Default")
      (node (ref "CIA_PB") (pin "6") (pinfunction "6_6") (pintype "passive"))
      (node (ref "U1") (pin "14") (pinfunction "PB4_14") (pintype "bidirectional"))
    )
    (net (code "82") (name "PB5") (class "Default")
      (node (ref "CIA_PB") (pin "7") (pinfunction "7_7") (pintype "passive"))
      (node (ref "U1") (pin "15") (pinfunction "PB5_15") (pintype "bidirectional"))
    )
    (net (code "83") (name "PB6") (class "Default")
      (node (ref "CIA_PB") (pin "8") (pinfunction "8_8") (pintype "passive"))
      (node (ref "U1") (pin "16") (pinfunction "PB6_16") (pintype "bidirectional"))
    )
    (net (code "84") (name "PB7") (class "Default")
      (node (ref "CIA_PB") (pin "9") (pinfunction "9_9") (pintype "passive"))
      (node (ref "U1") (pin "17") (pinfunction "PB7_17") (pintype "bidirectional"))
    )
    (net (code "85") (name "PHI2") (class "Default")
      (node (ref "PIC") (pin "3") (pinfunction "RA4/RA4/T0CKI/CMP2_3") (pintype "bidirectional"))
      (node (ref "U1") (pin "25") (pinfunction "PHI2_25") (pintype "bidirectional"))
      (node (ref "U2") (pin "25") (pinfunction "PHI2_25") (pintype "input"))
      (node (ref "U3") (pin "37") (pinfunction "PHI2_37") (pintype "input"))
      (node (ref "U7") (pin "9") (pinfunction "Q_9") (pintype "output"))
    )
    (net (code "86") (name "RESET") (class "Default")
      (node (ref "NANO") (pin "29") (pinfunction "D11/MOSI_29") (pintype "bidirectional"))
      (node (ref "R12") (pin "2") (pinfunction "2_2") (pintype "passive"))
      (node (ref "U8") (pin "13") (pinfunction "I_13") (pintype "input"))
    )
    (net (code "87") (name "R{slash}W") (class "Default")
      (node (ref "IC1") (pin "1") (pinfunction "DIR_1") (pintype "input"))
      (node (ref "NANO") (pin "30") (pinfunction "D12/MISO_30") (pintype "bidirectional"))
      (node (ref "U1") (pin "22") (pinfunction "R/W_22") (pintype "bidirectional"))
      (node (ref "U2") (pin "22") (pinfunction "R~{WB}_22") (pintype "input"))
      (node (ref "U3") (pin "34") (pinfunction "R~{WB}_34") (pintype "output"))
      (node (ref "U9") (pin "13") (pinfunction "B_13") (pintype "input"))
    )
    (net (code "88") (name "SERCLK") (class "Default")
      (node (ref "U1") (pin "40") (pinfunction "CNT_40") (pintype "bidirectional"))
      (node (ref "U2") (pin "18") (pinfunction "CB1_18") (pintype "bidirectional"))
    )
    (net (code "89") (name "SERDAT") (class "Default")
      (node (ref "U1") (pin "39") (pinfunction "SP_39") (pintype "bidirectional"))
      (node (ref "U2") (pin "19") (pinfunction "CB2_19") (pintype "bidirectional"))
    )
    (net (code "90") (name "TOD") (class "Default")
      (node (ref "NANO") (pin "1") (pinfunction "SCK/D13_1") (pintype "bidirectional"))
      (node (ref "U1") (pin "19") (pinfunction "TOD_19") (pintype "bidirectional"))
    )
    (net (code "91") (name "VCC") (class "Default")
      (node (ref "C1") (pin "1") (pinfunction "1_1") (pintype "passive"))
      (node (ref "C10") (pin "1") (pinfunction "1_1") (pintype "passive"))
      (node (ref "C11") (pin "1") (pinfunction "1_1") (pintype "passive"))
      (node (ref "C12") (pin "+") (pinfunction "+_+") (pintype "passive"))
      (node (ref "C14") (pin "1") (pinfunction "1_1") (pintype "passive"))
      (node (ref "C2") (pin "1") (pinfunction "1_1") (pintype "passive"))
      (node (ref "C3") (pin "1") (pinfunction "1_1") (pintype "passive"))
      (node (ref "C4") (pin "1") (pinfunction "1_1") (pintype "passive"))
      (node (ref "C7") (pin "1") (pinfunction "1_1") (pintype "passive"))
      (node (ref "C8") (pin "1") (pinfunction "1_1") (pintype "passive"))
      (node (ref "C9") (pin "1") (pinfunction "1_1") (pintype "passive"))
      (node (ref "CIA_PB") (pin "10") (pinfunction "10_10") (pintype "passive"))
      (node (ref "NANO") (pin "12") (pinfunction "5V_12") (pintype "power_in"))
      (node (ref "P2") (pin "E") (pinfunction "E_E") (pintype "passive"))
      (node (ref "PIC") (pin "14") (pinfunction "VDD_14") (pintype "power_in"))
      (node (ref "R10") (pin "1") (pinfunction "1_1") (pintype "passive"))
      (node (ref "R11") (pin "1") (pinfunction "1_1") (pintype "passive"))
      (node (ref "R9") (pin "1") (pinfunction "1_1") (pintype "passive"))
      (node (ref "SW1") (pin "1") (pinfunction "X_1") (pintype "bidirectional"))
      (node (ref "SW1") (pin "2") (pinfunction "X_2") (pintype "bidirectional"))
      (node (ref "U$5") (pin "P$2") (pinfunction "VDD_P$2") (pintype "power_in"))
      (node (ref "U1") (pin "20") (pinfunction "VCC_20") (pintype "bidirectional"))
      (node (ref "U10") (pin "16") (pinfunction "VCC_16") (pintype "power_in"))
      (node (ref "U2") (pin "20") (pinfunction "VDD_20") (pintype "power_in"))
      (node (ref "U2") (pin "24") (pinfunction "CS1_24") (pintype "input"))
      (node (ref "U3") (pin "38") (pinfunction "~{SOB}_38") (pintype "input"))
      (node (ref "U3") (pin "8") (pinfunction "VDD_8") (pintype "power_in"))
      (node (ref "U4") (pin "32") (pinfunction "VDD_32") (pintype "bidirectional"))
      (node (ref "U5") (pin "10") (pinfunction "SCL_10") (pintype "input"))
      (node (ref "U5") (pin "16") (pinfunction "VCC_16") (pintype "power_in"))
      (node (ref "U6") (pin "10") (pinfunction "SCL_10") (pintype "input"))
      (node (ref "U6") (pin "16") (pinfunction "VCC_16") (pintype "power_in"))
      (node (ref "U7") (pin "1") (pinfunction "CLR_1") (pintype "input"))
      (node (ref "U7") (pin "10") (pinfunction "PRE_10") (pintype "input"))
      (node (ref "U7") (pin "13") (pinfunction "CLR_13") (pintype "input"))
      (node (ref "U7") (pin "14") (pinfunction "VCC_14") (pintype "power_in"))
      (node (ref "U7") (pin "2") (pinfunction "D_2") (pintype "input"))
      (node (ref "U7") (pin "3") (pinfunction "CLK_3") (pintype "input"))
      (node (ref "U7") (pin "4") (pinfunction "PRE_4") (pintype "input"))
      (node (ref "U8") (pin "14") (pinfunction "VCC_14") (pintype "power_in"))
      (node (ref "U9") (pin "16") (pinfunction "VCC_16") (pintype "power_in"))
      (node (ref "VCC") (pin "1") (pinfunction "1_1") (pintype "passive"))
      (node (ref "VCC") (pin "2") (pinfunction "2_2") (pintype "passive"))
      (node (ref "VCC") (pin "3") (pinfunction "3_3") (pintype "passive"))
    )
    (net (code "92") (name "VIN") (class "Default")
      (node (ref "J1") (pin "3") (pinfunction "3_3") (pintype "passive"))
      (node (ref "NANO") (pin "15") (pinfunction "VIN_15") (pintype "power_in"))
    )
    (net (code "93") (name "VPB4") (class "Default")
      (node (ref "U$4") (pin "3") (pinfunction "Y_3") (pintype "bidirectional"))
      (node (ref "U$4") (pin "4") (pinfunction "Y_4") (pintype "bidirectional"))
      (node (ref "U2") (pin "14") (pinfunction "PB4_14") (pintype "bidirectional"))
    )
    (net (code "94") (name "VPB5") (class "Default")
      (node (ref "U$3") (pin "3") (pinfunction "Y_3") (pintype "bidirectional"))
      (node (ref "U$3") (pin "4") (pinfunction "Y_4") (pintype "bidirectional"))
      (node (ref "U2") (pin "15") (pinfunction "PB5_15") (pintype "bidirectional"))
    )
    (net (code "95") (name "VPB6") (class "Default")
      (node (ref "U$2") (pin "3") (pinfunction "Y_3") (pintype "bidirectional"))
      (node (ref "U$2") (pin "4") (pinfunction "Y_4") (pintype "bidirectional"))
      (node (ref "U2") (pin "16") (pinfunction "PB6_16") (pintype "bidirectional"))
    )
    (net (code "96") (name "VPB7") (class "Default")
      (node (ref "U$1") (pin "3") (pinfunction "Y_3") (pintype "bidirectional"))
      (node (ref "U$1") (pin "4") (pinfunction "Y_4") (pintype "bidirectional"))
      (node (ref "U2") (pin "17") (pinfunction "PB7_17") (pintype "bidirectional"))
    )
    (net (code "97") (name "unconnected-(NANO-3V3-Pad2)") (class "Default")
      (node (ref "NANO") (pin "2") (pinfunction "3V3_2") (pintype "output"))
    )
    (net (code "98") (name "unconnected-(NANO-ADC3{slash}A3-Pad7)") (class "Default")
      (node (ref "NANO") (pin "7") (pinfunction "ADC3/A3_7") (pintype "bidirectional"))
    )
    (net (code "99") (name "unconnected-(NANO-ADC5{slash}SCL{slash}A5-Pad9)") (class "Default")
      (node (ref "NANO") (pin "9") (pinfunction "ADC5/SCL/A5_9") (pintype "bidirectional"))
    )
    (net (code "100") (name "unconnected-(NANO-ADC6{slash}A6-Pad10)") (class "Default")
      (node (ref "NANO") (pin "10") (pinfunction "ADC6/A6_10") (pintype "bidirectional"))
    )
    (net (code "101") (name "unconnected-(NANO-ADC7{slash}A7-Pad11)") (class "Default")
      (node (ref "NANO") (pin "11") (pinfunction "ADC7/A7_11") (pintype "bidirectional"))
    )
    (net (code "102") (name "unconnected-(NANO-AREF-Pad3)") (class "Default")
      (node (ref "NANO") (pin "3") (pinfunction "AREF_3") (pintype "input"))
    )
    (net (code "103") (name "unconnected-(NANO-D0{slash}RX-Pad17)") (class "Default")
      (node (ref "NANO") (pin "17") (pinfunction "D0/RX_17") (pintype "bidirectional"))
    )
    (net (code "104") (name "unconnected-(NANO-D1{slash}TX-Pad16)") (class "Default")
      (node (ref "NANO") (pin "16") (pinfunction "D1/TX_16") (pintype "bidirectional"))
    )
    (net (code "105") (name "unconnected-(NANO-~{RESET}-Pad13)") (class "Default")
      (node (ref "NANO") (pin "13") (pinfunction "~{RESET}_13") (pintype "input"))
    )
    (net (code "106") (name "unconnected-(NANO-~{RESET}-Pad18)") (class "Default")
      (node (ref "NANO") (pin "18") (pinfunction "~{RESET}_18") (pintype "input"))
    )
    (net (code "107") (name "unconnected-(P1-PadA)") (class "Default")
      (node (ref "P1") (pin "A") (pinfunction "A_A") (pintype "passive"))
    )
    (net (code "108") (name "unconnected-(PIC-RA1{slash}AN1-Pad18)") (class "Default")
      (node (ref "PIC") (pin "18") (pinfunction "RA1/AN1_18") (pintype "bidirectional"))
    )
    (net (code "109") (name "unconnected-(U1-PA0-Pad2)") (class "Default")
      (node (ref "U1") (pin "2") (pinfunction "PA0_2") (pintype "bidirectional"))
    )
    (net (code "110") (name "unconnected-(U2A-PA4-Pad6)") (class "Default")
      (node (ref "U2") (pin "6") (pinfunction "PA4_6") (pintype "bidirectional"))
    )
    (net (code "111") (name "unconnected-(U2A-PA6-Pad8)") (class "Default")
      (node (ref "U2") (pin "8") (pinfunction "PA6_8") (pintype "bidirectional"))
    )
    (net (code "112") (name "unconnected-(U2A-PA7-Pad9)") (class "Default")
      (node (ref "U2") (pin "9") (pinfunction "PA7_9") (pintype "bidirectional"))
    )
    (net (code "113") (name "unconnected-(U2A-PB0-Pad10)") (class "Default")
      (node (ref "U2") (pin "10") (pinfunction "PB0_10") (pintype "bidirectional"))
    )
    (net (code "114") (name "unconnected-(U2A-PB1-Pad11)") (class "Default")
      (node (ref "U2") (pin "11") (pinfunction "PB1_11") (pintype "bidirectional"))
    )
    (net (code "115") (name "unconnected-(U2A-PB2-Pad12)") (class "Default")
      (node (ref "U2") (pin "12") (pinfunction "PB2_12") (pintype "bidirectional"))
    )
    (net (code "116") (name "unconnected-(U2A-PB3-Pad13)") (class "Default")
      (node (ref "U2") (pin "13") (pinfunction "PB3_13") (pintype "bidirectional"))
    )
    (net (code "117") (name "unconnected-(U3A-NC-Pad35)") (class "Default")
      (node (ref "U3") (pin "35") (pinfunction "NC_35") (pintype "no_connect"))
    )
    (net (code "118") (name "unconnected-(U3A-PHI1O-Pad3)") (class "Default")
      (node (ref "U3") (pin "3") (pinfunction "PHI1O_3") (pintype "output"))
    )
    (net (code "119") (name "unconnected-(U3A-PHI2O-Pad39)") (class "Default")
      (node (ref "U3") (pin "39") (pinfunction "PHI2O_39") (pintype "output"))
    )
    (net (code "120") (name "unconnected-(U3A-SYNC-Pad7)") (class "Default")
      (node (ref "U3") (pin "7") (pinfunction "SYNC_7") (pintype "output"))
    )
    (net (code "121") (name "unconnected-(U3A-~{MLB}-Pad5)") (class "Default")
      (node (ref "U3") (pin "5") (pinfunction "~{MLB}_5") (pintype "output"))
    )
    (net (code "122") (name "unconnected-(U3A-~{VPB}-Pad1)") (class "Default")
      (node (ref "U3") (pin "1") (pinfunction "~{VPB}_1") (pintype "output"))
    )
    (net (code "123") (name "unconnected-(U4-NC-Pad1)") (class "Default")
      (node (ref "U4") (pin "1") (pinfunction "NC_1") (pintype "bidirectional"))
    )
    (net (code "124") (name "unconnected-(U6A-QH*-Pad9)") (class "Default")
      (node (ref "U6") (pin "9") (pinfunction "QH*_9") (pintype "tri_state"))
    )
    (net (code "125") (name "unconnected-(U7A-Q-Pad5)") (class "Default")
      (node (ref "U7") (pin "5") (pinfunction "Q_5") (pintype "output"))
    )
    (net (code "126") (name "unconnected-(U7A-~{Q}-Pad6)") (class "Default")
      (node (ref "U7") (pin "6") (pinfunction "~{Q}_6") (pintype "output"))
    )
    (net (code "127") (name "unconnected-(U8B-O-Pad10)") (class "Default")
      (node (ref "U8") (pin "10") (pinfunction "O_10") (pintype "output"))
    )
    (net (code "128") (name "unconnected-(U8C-O-Pad8)") (class "Default")
      (node (ref "U8") (pin "8") (pinfunction "O_8") (pintype "output"))
    )
    (net (code "129") (name "unconnected-(U8F-O-Pad6)") (class "Default")
      (node (ref "U8") (pin "6") (pinfunction "O_6") (pintype "output"))
    )
    (net (code "130") (name "unconnected-(U9A-Y0-Pad4)") (class "Default")
      (node (ref "U9") (pin "4") (pinfunction "Y0_4") (pintype "output"))
    )
    (net (code "131") (name "unconnected-(U9A-Y1-Pad5)") (class "Default")
      (node (ref "U9") (pin "5") (pinfunction "Y1_5") (pintype "output"))
    )
    (net (code "132") (name "unconnected-(U9A-Y3-Pad7)") (class "Default")
      (node (ref "U9") (pin "7") (pinfunction "Y3_7") (pintype "output"))
    )
    (net (code "133") (name "unconnected-(U9B-Y1-Pad11)") (class "Default")
      (node (ref "U9") (pin "11") (pinfunction "Y1_11") (pintype "output"))
    )
    (net (code "134") (name "unconnected-(U9B-Y3-Pad9)") (class "Default")
      (node (ref "U9") (pin "9") (pinfunction "Y3_9") (pintype "output"))
    )
    (net (code "135") (name "unconnected-(U10A-Y0-Pad15)") (class "Default")
      (node (ref "U10") (pin "15") (pinfunction "Y0_15") (pintype "output"))
    )
    (net (code "136") (name "unconnected-(U10A-Y3-Pad12)") (class "Default")
      (node (ref "U10") (pin "12") (pinfunction "Y3_12") (pintype "output"))
    )
    (net (code "137") (name "unconnected-(U10A-Y4-Pad11)") (class "Default")
      (node (ref "U10") (pin "11") (pinfunction "Y4_11") (pintype "output"))
    )
    (net (code "138") (name "unconnected-(U10A-Y5-Pad10)") (class "Default")
      (node (ref "U10") (pin "10") (pinfunction "Y5_10") (pintype "output"))
    )
    (net (code "139") (name "unconnected-(U10A-Y6-Pad9)") (class "Default")
      (node (ref "U10") (pin "9") (pinfunction "Y6_9") (pintype "output"))
    )
    (net (code "140") (name "unconnected-(U10A-Y7-Pad7)") (class "Default")
      (node (ref "U10") (pin "7") (pinfunction "Y7_7") (pintype "output"))
    )
    (net (code "141") (name "{slash}CE") (class "Default")
      (node (ref "NANO") (pin "28") (pinfunction "D10/OC1B/~{SS}_28") (pintype "bidirectional"))
      (node (ref "U4") (pin "22") (pinfunction "CE1_22") (pintype "bidirectional"))
    )
    (net (code "142") (name "{slash}CIA") (class "Default")
      (node (ref "IC1") (pin "19") (pinfunction "G_19") (pintype "input"))
      (node (ref "U1") (pin "23") (pinfunction "/CS_23") (pintype "bidirectional"))
      (node (ref "U10") (pin "14") (pinfunction "Y1_14") (pintype "output"))
    )
    (net (code "143") (name "{slash}CIARES") (class "Default")
      (node (ref "U1") (pin "34") (pinfunction "/RES_34") (pintype "bidirectional"))
      (node (ref "U2") (pin "7") (pinfunction "PA5_7") (pintype "bidirectional"))
    )
    (net (code "144") (name "{slash}FLAG") (class "Default")
      (node (ref "U1") (pin "24") (pinfunction "/FLAG_24") (pintype "bidirectional"))
      (node (ref "U2") (pin "39") (pinfunction "CA2_39") (pintype "bidirectional"))
    )
    (net (code "145") (name "{slash}IRQ") (class "Default")
      (node (ref "U1") (pin "21") (pinfunction "/IRQ_21") (pintype "bidirectional"))
      (node (ref "U3") (pin "4") (pinfunction "~{IRQB}_4") (pintype "input"))
    )
    (net (code "146") (name "{slash}OE") (class "Default")
      (node (ref "U4") (pin "24") (pinfunction "OE_24") (pintype "bidirectional"))
      (node (ref "U9") (pin "10") (pinfunction "Y2_10") (pintype "output"))
    )
    (net (code "147") (name "{slash}PC") (class "Default")
      (node (ref "U1") (pin "18") (pinfunction "/PC_18") (pintype "bidirectional"))
      (node (ref "U2") (pin "40") (pinfunction "CA1_40") (pintype "bidirectional"))
    )
    (net (code "148") (name "{slash}PHI2") (class "Default")
      (node (ref "U7") (pin "12") (pinfunction "D_12") (pintype "input"))
      (node (ref "U7") (pin "8") (pinfunction "~{Q}_8") (pintype "output"))
      (node (ref "U9") (pin "14") (pinfunction "A_14") (pintype "input"))
    )
    (net (code "149") (name "{slash}RES") (class "Default")
      (node (ref "U2") (pin "34") (pinfunction "~{RESB}_34") (pintype "input"))
      (node (ref "U3") (pin "40") (pinfunction "~{RESB}_40") (pintype "input"))
      (node (ref "U8") (pin "12") (pinfunction "O_12") (pintype "output"))
    )
    (net (code "150") (name "{slash}VIA") (class "Default")
      (node (ref "U10") (pin "13") (pinfunction "Y2_13") (pintype "output"))
      (node (ref "U2") (pin "23") (pinfunction "~{CS2B}_23") (pintype "input"))
    )
    (net (code "151") (name "{slash}VIAIRQ") (class "Default")
      (node (ref "U2") (pin "21") (pinfunction "~{IRQB}_21") (pintype "output"))
      (node (ref "U3") (pin "6") (pinfunction "~{NMIB}_6") (pintype "input"))
    )
    (net (code "152") (name "{slash}WE") (class "Default")
      (node (ref "U4") (pin "29") (pinfunction "WE_29") (pintype "bidirectional"))
      (node (ref "U9") (pin "12") (pinfunction "Y0_12") (pintype "output"))
    )
  )
)
